# STC12C5A60S2.net
KiCad netlist of a schematic drawn in Altium Designer
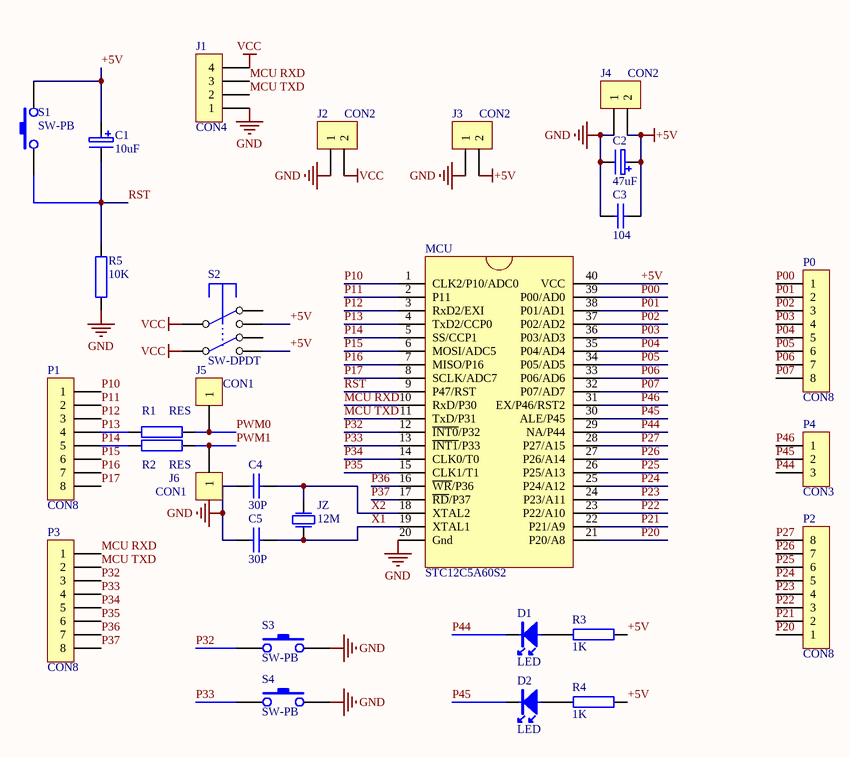
[diagram p0: STC12C5A60S2最小系统.SchDoc]

(export (version "E")
  (design (tool "Eeschema 10.0.6"))
  (components
    (comp (ref "C1") (value "10uF") (footprint "CAO1") (libsource (lib "C电容") (part "CAP3")))
    (comp (ref "C2") (value "47uF") (footprint "CAO1") (libsource (lib "C电容") (part "CAP3")))
    (comp (ref "C3") (value "104") (footprint "CAP1") (libsource (lib "C电容") (part "CAP1")))
    (comp (ref "C4") (value "30P") (footprint "CAP1") (libsource (lib "C电容") (part "CAP1")))
    (comp (ref "C5") (value "30P") (footprint "CAP1") (libsource (lib "C电容") (part "CAP1")))
    (comp (ref "D1") (value "LED") (footprint "LED2") (libsource (lib "Diode二极管") (part "LED")))
    (comp (ref "D2") (value "LED") (footprint "LED2") (libsource (lib "Diode二极管") (part "LED")))
    (comp (ref "J1")
      (value "CON4")
      (footprint "sip-4")
      (description "Connector")
      (libsource (lib "接口") (part "CON4"))
    )
    (comp (ref "J2")
      (value "CON2")
      (footprint "sip-2")
      (description "Connector")
      (libsource (lib "接口") (part "CON2"))
    )
    (comp (ref "J3")
      (value "CON2")
      (footprint "sip-2")
      (description "Connector")
      (libsource (lib "接口") (part "CON2"))
    )
    (comp (ref "J4")
      (value "CON2")
      (footprint "sip-2")
      (description "Connector")
      (libsource (lib "接口") (part "CON2"))
    )
    (comp (ref "J5")
      (value "CON1")
      (footprint "SIP-1")
      (description "Connector")
      (libsource (lib "接口") (part "CON1"))
    )
    (comp (ref "J6")
      (value "CON1")
      (footprint "SIP-1")
      (description "Connector")
      (libsource (lib "") (part "CON1_1"))
    )
    (comp (ref "JZ")
      (value "12M")
      (footprint "JZ1")
      (description "6.0000 8.000  11.0592  12.0000 24.000")
      (libsource (lib "J晶振") (part "CRY1"))
    )
    (comp (ref "MCU")
      (value "STC12C5A60S2")
      (footprint "DIP-40")
      (libsource (lib "MCU") (part "STC12C5AXXS2"))
    )
    (comp (ref "P0")
      (value "CON8")
      (footprint "sip-8")
      (description "Connector")
      (libsource (lib "") (part "CON8_1"))
    )
    (comp (ref "P1")
      (value "CON8")
      (footprint "sip-8")
      (description "Connector")
      (libsource (lib "接口") (part "CON8"))
    )
    (comp (ref "P2")
      (value "CON8")
      (footprint "sip-8")
      (description "Connector")
      (libsource (lib "") (part "CON8_2"))
    )
    (comp (ref "P3")
      (value "CON8")
      (footprint "sip-8")
      (description "Connector")
      (libsource (lib "接口") (part "CON8"))
    )
    (comp (ref "P4")
      (value "CON3")
      (footprint "sip-3")
      (description "Connector")
      (libsource (lib "接口") (part "CON3"))
    )
    (comp (ref "R1") (value "RES") (footprint "AXIAL0.3") (libsource (lib "R电阻") (part "RES")))
    (comp (ref "R2") (value "RES") (footprint "AXIAL0.3") (libsource (lib "R电阻") (part "RES")))
    (comp (ref "R3") (value "1K") (footprint "AXIAL0.3") (libsource (lib "R电阻") (part "RES")))
    (comp (ref "R4") (value "1K") (footprint "AXIAL0.3") (libsource (lib "R电阻") (part "RES")))
    (comp (ref "R5") (value "10K") (footprint "AXIAL0.3") (libsource (lib "R电阻") (part "RES")))
    (comp (ref "S1") (value "SW-PB") (footprint "SW6*6") (libsource (lib "SW开关") (part "SW-PB")))
    (comp (ref "S2") (value "SW-DPDT") (footprint "SW3") (libsource (lib "SW开关") (part "SW-DPDT")))
    (comp (ref "S3") (value "SW-PB") (footprint "SW6*6") (libsource (lib "SW开关") (part "SW-PB")))
    (comp (ref "S4") (value "SW-PB") (footprint "SW6*6") (libsource (lib "SW开关") (part "SW-PB")))
  )
  (nets
    (net (code "1") (name "+5V") (class "Default")
      (node (ref "C1") (pin "1") (pintype "passive"))
      (node (ref "C2") (pin "1") (pintype "passive"))
      (node (ref "C3") (pin "1") (pinfunction "1_1") (pintype "passive"))
      (node (ref "J3") (pin "2") (pinfunction "2_2") (pintype "passive"))
      (node (ref "J4") (pin "2") (pinfunction "2_2") (pintype "passive"))
      (node (ref "MCU") (pin "40") (pinfunction "VCC_40") (pintype "passive"))
      (node (ref "R3") (pin "2") (pinfunction "2_2") (pintype "passive"))
      (node (ref "R4") (pin "2") (pinfunction "2_2") (pintype "passive"))
      (node (ref "S1") (pin "2") (pinfunction "2_2") (pintype "passive"))
      (node (ref "S2") (pin "1") (pinfunction "1_1") (pintype "passive"))
      (node (ref "S2") (pin "4") (pinfunction "4_4") (pintype "passive"))
    )
    (net (code "2") (name "/MCU RXD") (class "Default")
      (node (ref "J1") (pin "3") (pinfunction "3_3") (pintype "passive"))
      (node (ref "MCU") (pin "10") (pinfunction "RxD/P30_10") (pintype "passive"))
      (node (ref "P3") (pin "1") (pinfunction "1_1") (pintype "passive"))
    )
    (net (code "3") (name "/MCU TXD") (class "Default")
      (node (ref "J1") (pin "2") (pinfunction "2_2") (pintype "passive"))
      (node (ref "MCU") (pin "11") (pinfunction "TxD/P31_11") (pintype "passive"))
      (node (ref "P3") (pin "2") (pinfunction "2_2") (pintype "passive"))
    )
    (net (code "4") (name "/P00") (class "Default")
      (node (ref "MCU") (pin "39") (pinfunction "P00/AD0_39") (pintype "passive"))
      (node (ref "P0") (pin "1") (pinfunction "1_1") (pintype "passive"))
    )
    (net (code "5") (name "/P01") (class "Default")
      (node (ref "MCU") (pin "38") (pinfunction "P01/AD1_38") (pintype "passive"))
      (node (ref "P0") (pin "2") (pinfunction "2_2") (pintype "passive"))
    )
    (net (code "6") (name "/P02") (class "Default")
      (node (ref "MCU") (pin "37") (pinfunction "P02/AD2_37") (pintype "passive"))
      (node (ref "P0") (pin "3") (pinfunction "3_3") (pintype "passive"))
    )
    (net (code "7") (name "/P03") (class "Default")
      (node (ref "MCU") (pin "36") (pinfunction "P03/AD3_36") (pintype "passive"))
      (node (ref "P0") (pin "4") (pinfunction "4_4") (pintype "passive"))
    )
    (net (code "8") (name "/P04") (class "Default")
      (node (ref "MCU") (pin "35") (pinfunction "P04/AD4_35") (pintype "passive"))
      (node (ref "P0") (pin "5") (pinfunction "5_5") (pintype "passive"))
    )
    (net (code "9") (name "/P05") (class "Default")
      (node (ref "MCU") (pin "34") (pinfunction "P05/AD5_34") (pintype "passive"))
      (node (ref "P0") (pin "6") (pinfunction "6_6") (pintype "passive"))
    )
    (net (code "10") (name "/P06") (class "Default")
      (node (ref "MCU") (pin "33") (pinfunction "P06/AD6_33") (pintype "passive"))
      (node (ref "P0") (pin "7") (pinfunction "7_7") (pintype "passive"))
    )
    (net (code "11") (name "/P07") (class "Default")
      (node (ref "MCU") (pin "32") (pinfunction "P07/AD7_32") (pintype "passive"))
      (node (ref "P0") (pin "8") (pinfunction "8_8") (pintype "passive"))
    )
    (net (code "12") (name "/P10") (class "Default")
      (node (ref "MCU") (pin "1") (pinfunction "CLK2/P10/ADC0_1") (pintype "passive"))
      (node (ref "P1") (pin "1") (pinfunction "1_1") (pintype "passive"))
    )
    (net (code "13") (name "/P11") (class "Default")
      (node (ref "MCU") (pin "2") (pinfunction "P11_2") (pintype "passive"))
      (node (ref "P1") (pin "2") (pinfunction "2_2") (pintype "passive"))
    )
    (net (code "14") (name "/P12") (class "Default")
      (node (ref "MCU") (pin "3") (pinfunction "RxD2/EXI_3") (pintype "passive"))
      (node (ref "P1") (pin "3") (pinfunction "3_3") (pintype "passive"))
    )
    (net (code "15") (name "/P13") (class "Default")
      (node (ref "MCU") (pin "4") (pinfunction "TxD2/CCP0_4") (pintype "passive"))
      (node (ref "P1") (pin "4") (pinfunction "4_4") (pintype "passive"))
      (node (ref "R1") (pin "1") (pinfunction "1_1") (pintype "passive"))
    )
    (net (code "16") (name "/P14") (class "Default")
      (node (ref "MCU") (pin "5") (pinfunction "SS/CCP1_5") (pintype "passive"))
      (node (ref "P1") (pin "5") (pinfunction "5_5") (pintype "passive"))
      (node (ref "R2") (pin "1") (pinfunction "1_1") (pintype "passive"))
    )
    (net (code "17") (name "/P15") (class "Default")
      (node (ref "MCU") (pin "6") (pinfunction "MOSI/ADC5_6") (pintype "passive"))
      (node (ref "P1") (pin "6") (pinfunction "6_6") (pintype "passive"))
    )
    (net (code "18") (name "/P16") (class "Default")
      (node (ref "MCU") (pin "7") (pinfunction "MISO/P16_7") (pintype "passive"))
      (node (ref "P1") (pin "7") (pinfunction "7_7") (pintype "passive"))
    )
    (net (code "19") (name "/P17") (class "Default")
      (node (ref "MCU") (pin "8") (pinfunction "SCLK/ADC7_8") (pintype "passive"))
      (node (ref "P1") (pin "8") (pinfunction "8_8") (pintype "passive"))
    )
    (net (code "20") (name "/P20") (class "Default")
      (node (ref "MCU") (pin "21") (pinfunction "P20/A8_21") (pintype "passive"))
      (node (ref "P2") (pin "1") (pinfunction "1_1") (pintype "passive"))
    )
    (net (code "21") (name "/P21") (class "Default")
      (node (ref "MCU") (pin "22") (pinfunction "P21/A9_22") (pintype "passive"))
      (node (ref "P2") (pin "2") (pinfunction "2_2") (pintype "passive"))
    )
    (net (code "22") (name "/P22") (class "Default")
      (node (ref "MCU") (pin "23") (pinfunction "P22/A10_23") (pintype "passive"))
      (node (ref "P2") (pin "3") (pinfunction "3_3") (pintype "passive"))
    )
    (net (code "23") (name "/P23") (class "Default")
      (node (ref "MCU") (pin "24") (pinfunction "P23/A11_24") (pintype "passive"))
      (node (ref "P2") (pin "4") (pinfunction "4_4") (pintype "passive"))
    )
    (net (code "24") (name "/P24") (class "Default")
      (node (ref "MCU") (pin "25") (pinfunction "P24/A12_25") (pintype "passive"))
      (node (ref "P2") (pin "5") (pinfunction "5_5") (pintype "passive"))
    )
    (net (code "25") (name "/P25") (class "Default")
      (node (ref "MCU") (pin "26") (pinfunction "P25/A13_26") (pintype "passive"))
      (node (ref "P2") (pin "6") (pinfunction "6_6") (pintype "passive"))
    )
    (net (code "26") (name "/P26") (class "Default")
      (node (ref "MCU") (pin "27") (pinfunction "P26/A14_27") (pintype "passive"))
      (node (ref "P2") (pin "7") (pinfunction "7_7") (pintype "passive"))
    )
    (net (code "27") (name "/P27") (class "Default")
      (node (ref "MCU") (pin "28") (pinfunction "P27/A15_28") (pintype "passive"))
      (node (ref "P2") (pin "8") (pinfunction "8_8") (pintype "passive"))
    )
    (net (code "28") (name "/P32") (class "Default")
      (node (ref "MCU") (pin "12") (pinfunction "~{INT0}/P32_12") (pintype "passive"))
      (node (ref "P3") (pin "3") (pinfunction "3_3") (pintype "passive"))
      (node (ref "S3") (pin "1") (pinfunction "1_1") (pintype "passive"))
    )
    (net (code "29") (name "/P33") (class "Default")
      (node (ref "MCU") (pin "13") (pinfunction "~{INT1}/P33_13") (pintype "passive"))
      (node (ref "P3") (pin "4") (pinfunction "4_4") (pintype "passive"))
      (node (ref "S4") (pin "1") (pinfunction "1_1") (pintype "passive"))
    )
    (net (code "30") (name "/P34") (class "Default")
      (node (ref "MCU") (pin "14") (pinfunction "CLK0/T0_14") (pintype "passive"))
      (node (ref "P3") (pin "5") (pinfunction "5_5") (pintype "passive"))
    )
    (net (code "31") (name "/P35") (class "Default")
      (node (ref "MCU") (pin "15") (pinfunction "CLK1/T1_15") (pintype "passive"))
      (node (ref "P3") (pin "6") (pinfunction "6_6") (pintype "passive"))
    )
    (net (code "32") (name "/P36") (class "Default")
      (node (ref "MCU") (pin "16") (pinfunction "~{WR}/P36_16") (pintype "passive"))
      (node (ref "P3") (pin "7") (pinfunction "7_7") (pintype "passive"))
    )
    (net (code "33") (name "/P37") (class "Default")
      (node (ref "MCU") (pin "17") (pinfunction "~{RD}/P37_17") (pintype "passive"))
      (node (ref "P3") (pin "8") (pinfunction "8_8") (pintype "passive"))
    )
    (net (code "34") (name "/P44") (class "Default")
      (node (ref "D1") (pin "2") (pinfunction "2_2") (pintype "passive"))
      (node (ref "MCU") (pin "29") (pinfunction "NA/P44_29") (pintype "passive"))
      (node (ref "P4") (pin "3") (pinfunction "3_3") (pintype "passive"))
    )
    (net (code "35") (name "/P45") (class "Default")
      (node (ref "D2") (pin "2") (pinfunction "2_2") (pintype "passive"))
      (node (ref "MCU") (pin "30") (pinfunction "ALE/P45_30") (pintype "passive"))
      (node (ref "P4") (pin "2") (pinfunction "2_2") (pintype "passive"))
    )
    (net (code "36") (name "/P46") (class "Default")
      (node (ref "MCU") (pin "31") (pinfunction "EX/P46/RST2_31") (pintype "passive"))
      (node (ref "P4") (pin "1") (pinfunction "1_1") (pintype "passive"))
    )
    (net (code "37") (name "/PWM0") (class "Default")
      (node (ref "J5") (pin "1") (pinfunction "1_1") (pintype "passive"))
      (node (ref "R1") (pin "2") (pinfunction "2_2") (pintype "passive"))
    )
    (net (code "38") (name "/PWM1") (class "Default")
      (node (ref "J6") (pin "1") (pinfunction "1_1") (pintype "passive"))
      (node (ref "R2") (pin "2") (pinfunction "2_2") (pintype "passive"))
    )
    (net (code "39") (name "/RST") (class "Default")
      (node (ref "C1") (pin "2") (pintype "passive"))
      (node (ref "MCU") (pin "9") (pinfunction "P47/RST_9") (pintype "passive"))
      (node (ref "R5") (pin "2") (pinfunction "2_2") (pintype "passive"))
      (node (ref "S1") (pin "1") (pinfunction "1_1") (pintype "passive"))
    )
    (net (code "40") (name "/X1") (class "Default")
      (node (ref "C5") (pin "1") (pinfunction "1_1") (pintype "passive"))
      (node (ref "JZ") (pin "2") (pinfunction "P2_2") (pintype "passive"))
      (node (ref "MCU") (pin "19") (pinfunction "XTAL1_19") (pintype "passive"))
    )
    (net (code "41") (name "/X2") (class "Default")
      (node (ref "C4") (pin "1") (pinfunction "1_1") (pintype "passive"))
      (node (ref "JZ") (pin "1") (pinfunction "P1_1") (pintype "passive"))
      (node (ref "MCU") (pin "18") (pinfunction "XTAL2_18") (pintype "passive"))
    )
    (net (code "42") (name "GND") (class "Default")
      (node (ref "C2") (pin "2") (pintype "passive"))
      (node (ref "C3") (pin "2") (pinfunction "2_2") (pintype "passive"))
      (node (ref "C4") (pin "2") (pinfunction "2_2") (pintype "passive"))
      (node (ref "C5") (pin "2") (pinfunction "2_2") (pintype "passive"))
      (node (ref "J1") (pin "1") (pinfunction "1_1") (pintype "passive"))
      (node (ref "J2") (pin "1") (pinfunction "1_1") (pintype "passive"))
      (node (ref "J3") (pin "1") (pinfunction "1_1") (pintype "passive"))
      (node (ref "J4") (pin "1") (pinfunction "1_1") (pintype "passive"))
      (node (ref "MCU") (pin "20") (pinfunction "Gnd_20") (pintype "passive"))
      (node (ref "R5") (pin "1") (pinfunction "1_1") (pintype "passive"))
      (node (ref "S3") (pin "2") (pinfunction "2_2") (pintype "passive"))
      (node (ref "S4") (pin "2") (pinfunction "2_2") (pintype "passive"))
    )
    (net (code "43") (name "Net-(D1-Pad1)") (class "Default")
      (node (ref "D1") (pin "1") (pinfunction "1_1") (pintype "passive"))
      (node (ref "R3") (pin "1") (pinfunction "1_1") (pintype "passive"))
    )
    (net (code "44") (name "Net-(D2-Pad1)") (class "Default")
      (node (ref "D2") (pin "1") (pinfunction "1_1") (pintype "passive"))
      (node (ref "R4") (pin "1") (pinfunction "1_1") (pintype "passive"))
    )
    (net (code "45") (name "VCC") (class "Default")
      (node (ref "J1") (pin "4") (pinfunction "4_4") (pintype "passive"))
      (node (ref "J2") (pin "2") (pinfunction "2_2") (pintype "passive"))
      (node (ref "S2") (pin "2") (pinfunction "2_2") (pintype "passive"))
      (node (ref "S2") (pin "5") (pinfunction "5_5") (pintype "passive"))
    )
    (net (code "46") (name "unconnected-(S2-Pad0)") (class "Default")
      (node (ref "S2") (pin "0") (pinfunction "0_0") (pintype "passive"))
    )
    (net (code "47") (name "unconnected-(S2-Pad3)") (class "Default")
      (node (ref "S2") (pin "3") (pinfunction "3_3") (pintype "passive"))
    )
  )
)
